# sensors.net
KiCad netlist of a schematic drawn in Altium Designer
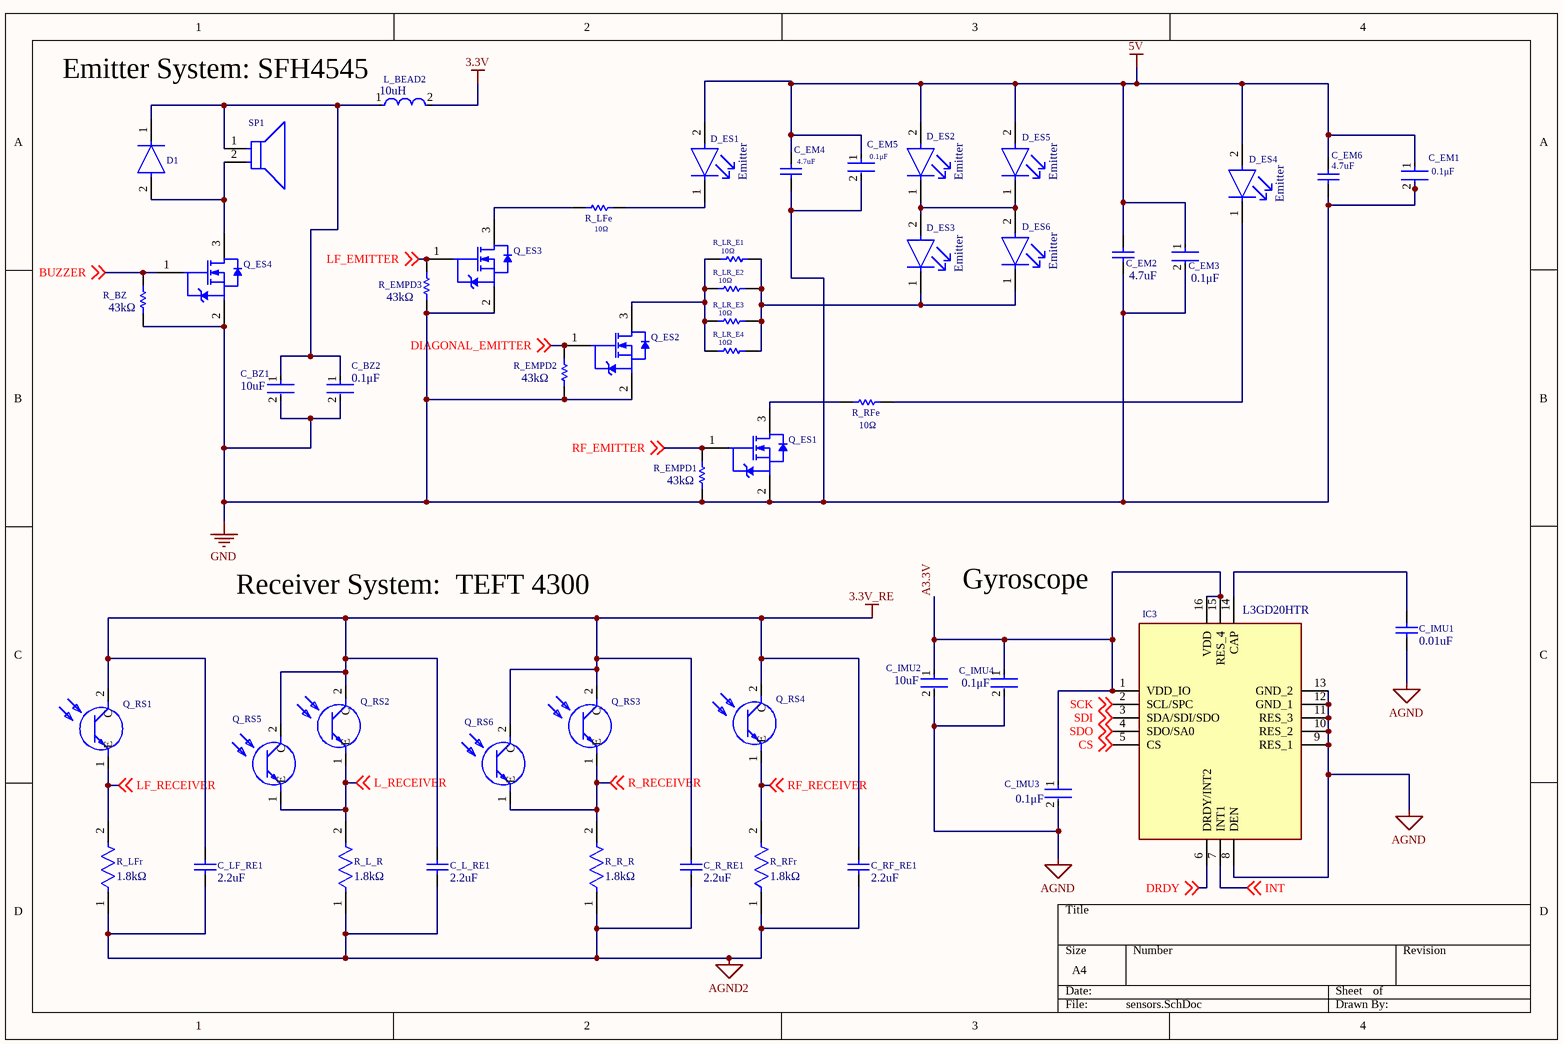
[diagram p0: sensors.SchDoc]

(export (version "E")
  (design (tool "Eeschema 10.0.6"))
  (components
    (comp (ref "C_BZ1")
      (value "10uF")
      (footprint "FP-C0805C-DG-MFG")
      (description "CAP CER 10UF 10V X5R 0805")
      (fields (field (name "TOLERANCE") "10%") (field (name "MANUFACTURER PART NUMBER") "C0805C106K8PACTU"))
      (libsource (lib "Altium Content Vault") (part "11868f565c42a9108669ba33697ecf6"))
    )
    (comp (ref "C_BZ2")
      (value "0.1μF")
      (footprint "FP-C0805C-DN-MFG")
      (description "CAP CER 0.1UF 10V 5% X7R 0805")
      (fields (field (name "MANUFACTURER") "KEMET") (field (name "TOLERANCE") "0.05"))
      (libsource (lib "Altium Content Vault") (part "b4654b650e69147ec39a6b967a45e02"))
    )
    (comp (ref "C_EM1")
      (value "0.1μF")
      (footprint "FP-C0805C-DN-MFG")
      (description "CAP CER 0.1UF 10V 5% X7R 0805")
      (fields (field (name "MANUFACTURER") "KEMET") (field (name "TOLERANCE") "0.05"))
      (libsource (lib "Altium Content Vault") (part "b4654b650e69147ec39a6b967a45e02"))
    )
    (comp (ref "C_EM2")
      (value "4.7uF")
      (footprint "CAPC2013X145X50NL20T25")
      (fields (field (name "PART NUMBER") "C0805C475M3PACTU") (field (name "MANUFACTURER") "Kemet"))
      (libsource (lib "Altium Content Vault") (part "CAP"))
    )
    (comp (ref "C_EM3")
      (value "0.1μF")
      (footprint "FP-C0805C-DN-MFG")
      (description "CAP CER 0.1UF 10V 5% X7R 0805")
      (fields (field (name "MANUFACTURER") "KEMET") (field (name "TOLERANCE") "0.05"))
      (libsource (lib "Altium Content Vault") (part "b4654b650e69147ec39a6b967a45e02"))
    )
    (comp (ref "C_EM4")
      (value "4.7uF")
      (footprint "CAPC2013X145X50NL20T25")
      (fields (field (name "PART NUMBER") "C0805C475M3PACTU") (field (name "MANUFACTURER") "Kemet"))
      (libsource (lib "Altium Content Vault") (part "CAP"))
    )
    (comp (ref "C_EM5")
      (value "0.1μF")
      (footprint "FP-C0805C-DN-MFG")
      (description "CAP CER 0.1UF 10V 5% X7R 0805")
      (fields (field (name "MANUFACTURER") "KEMET") (field (name "TOLERANCE") "0.05"))
      (libsource (lib "Altium Content Vault") (part "b4654b650e69147ec39a6b967a45e02"))
    )
    (comp (ref "C_EM6")
      (value "4.7uF")
      (footprint "CAPC2013X145X50NL20T25")
      (fields (field (name "PART NUMBER") "C0805C475M3PACTU") (field (name "MANUFACTURER") "Kemet"))
      (libsource (lib "Altium Content Vault") (part "CAP"))
    )
    (comp (ref "C_IMU1")
      (value "0.01uF")
      (footprint "CAPC2013X88X50LL20T25")
      (fields (field (name "MANUFACTURER") "Kemet") (field (name "PART NUMBER") "C0805C103K5RACTU"))
      (libsource (lib "Altium Content Vault") (part "CAP"))
    )
    (comp (ref "C_IMU2")
      (value "10uF")
      (footprint "FP-C0805C-DG-MFG")
      (description "CAP CER 10UF 10V X5R 0805")
      (fields (field (name "TOLERANCE") "10%") (field (name "MANUFACTURER PART NUMBER") "C0805C106K8PACTU"))
      (libsource (lib "Altium Content Vault") (part "11868f565c42a9108669ba33697ecf6"))
    )
    (comp (ref "C_IMU3")
      (value "0.1μF")
      (footprint "FP-C0805C-DN-MFG")
      (description "CAP CER 0.1UF 10V 5% X7R 0805")
      (fields (field (name "MANUFACTURER") "KEMET") (field (name "TOLERANCE") "0.05"))
      (libsource (lib "Altium Content Vault") (part "b4654b650e69147ec39a6b967a45e02"))
    )
    (comp (ref "C_IMU4")
      (value "0.1μF")
      (footprint "FP-C0805C-DN-MFG")
      (description "CAP CER 0.1UF 10V 5% X7R 0805")
      (fields (field (name "MANUFACTURER") "KEMET") (field (name "TOLERANCE") "0.05"))
      (libsource (lib "Altium Content Vault") (part "b4654b650e69147ec39a6b967a45e02"))
    )
    (comp (ref "C_LF_RE1")
      (value "2.2uF")
      (footprint "CAPC2013X145X50ML20T25")
      (fields (field (name "PART NUMBER") "C0805C225K9PACTU") (field (name "MANUFACTURER") "Kemet"))
      (libsource (lib "Altium Content Vault") (part "CAP"))
    )
    (comp (ref "C_L_RE1")
      (value "2.2uF")
      (footprint "CAPC2013X145X50ML20T25")
      (fields (field (name "PART NUMBER") "C0805C225K9PACTU") (field (name "MANUFACTURER") "Kemet"))
      (libsource (lib "Altium Content Vault") (part "CAP"))
    )
    (comp (ref "C_RF_RE1")
      (value "2.2uF")
      (footprint "CAPC2013X145X50ML20T25")
      (fields (field (name "PART NUMBER") "C0805C225K9PACTU") (field (name "MANUFACTURER") "Kemet"))
      (libsource (lib "Altium Content Vault") (part "CAP"))
    )
    (comp (ref "C_R_RE1")
      (value "2.2uF")
      (footprint "CAPC2013X145X50ML20T25")
      (fields (field (name "PART NUMBER") "C0805C225K9PACTU") (field (name "MANUFACTURER") "Kemet"))
      (libsource (lib "Altium Content Vault") (part "CAP"))
    )
    (comp (ref "D1")
      (value "1N4148W-TP")
      (footprint "FP-SOD-123-IPC_A")
      (description "DIODE GEN PURP 100V 150MA SOD123")
      (libsource (lib "Altium Content Vault") (part "d7152d700b627762746794eb795d46e"))
    )
    (comp (ref "D_ES1")
      (value "Emitter")
      (footprint "FP-SFH_4556-MFG")
      (description "EMITTER IR 950NM 100MA RADIAL")
      (fields (field (name "MANUFACTURER PART NUMBER") "SFH 4545") (field (name "MANUFACTURER") "Osram Opto"))
      (libsource (lib "Altium Content Vault") (part "8706943c75ba83719d021d2fdc84c58"))
    )
    (comp (ref "D_ES2")
      (value "Emitter")
      (footprint "FP-SFH_4556-MFG")
      (description "EMITTER IR 950NM 100MA RADIAL")
      (fields (field (name "MANUFACTURER PART NUMBER") "SFH 4545") (field (name "MANUFACTURER") "Osram Opto"))
      (libsource (lib "Altium Content Vault") (part "8706943c75ba83719d021d2fdc84c58"))
    )
    (comp (ref "D_ES3")
      (value "Emitter")
      (footprint "FP-SFH_4556-MFG")
      (description "EMITTER IR 950NM 100MA RADIAL")
      (fields (field (name "MANUFACTURER PART NUMBER") "SFH 4545") (field (name "MANUFACTURER") "Osram Opto"))
      (libsource (lib "Altium Content Vault") (part "8706943c75ba83719d021d2fdc84c58"))
    )
    (comp (ref "D_ES4")
      (value "Emitter")
      (footprint "FP-SFH_4556-MFG")
      (description "EMITTER IR 950NM 100MA RADIAL")
      (fields (field (name "MANUFACTURER PART NUMBER") "SFH 4545") (field (name "MANUFACTURER") "Osram Opto"))
      (libsource (lib "Altium Content Vault") (part "8706943c75ba83719d021d2fdc84c58"))
    )
    (comp (ref "D_ES5")
      (value "Emitter")
      (footprint "FP-SFH_4556-MFG")
      (description "EMITTER IR 950NM 100MA RADIAL")
      (fields (field (name "MANUFACTURER PART NUMBER") "SFH 4545") (field (name "MANUFACTURER") "Osram Opto"))
      (libsource (lib "Altium Content Vault") (part "8706943c75ba83719d021d2fdc84c58"))
    )
    (comp (ref "D_ES6")
      (value "Emitter")
      (footprint "FP-SFH_4556-MFG")
      (description "EMITTER IR 950NM 100MA RADIAL")
      (fields (field (name "MANUFACTURER PART NUMBER") "SFH 4545") (field (name "MANUFACTURER") "Osram Opto"))
      (libsource (lib "Altium Content Vault") (part "8706943c75ba83719d021d2fdc84c58"))
    )
    (comp (ref "IC3")
      (value "L3GD20HTR")
      (footprint "SamacSys:H3LIS100DLTR")
      (description "Integrated Circuit")
      (fields (field (name "MOUSER PART NUMBER") "511-L3GD20HTR"))
      (libsource (lib "*") (part "L3GD20HTR"))
    )
    (comp (ref "L_BEAD2")
      (value "10uH")
      (footprint "FP-LB2012-1_25-0_2-MFG")
      (description "SMD Inductors 10uH ±10% 0.15A 0.468Ω 0805")
      (fields (field (name "TOLERANCE") "10%") (field (name "Comment") "LBR2012T100K"))
      (libsource (lib "Altium Content Vault") (part "725321dda6339637d4d059423bc1c3c"))
    )
    (comp (ref "Q_ES1")
      (value "FDV303N")
      (footprint "FAIR-FDV303N-3_V")
      (fields (field (name "MANUFACTURER") "Fairchild"))
      (libsource (lib "Altium Content Vault") (part "NEMOS-GSD-3_D"))
    )
    (comp (ref "Q_ES2")
      (value "FDV303N")
      (footprint "FAIR-FDV303N-3_V")
      (fields (field (name "MANUFACTURER") "Fairchild"))
      (libsource (lib "Altium Content Vault") (part "NEMOS-GSD-3_D"))
    )
    (comp (ref "Q_ES3")
      (value "FDV303N")
      (footprint "FAIR-FDV303N-3_V")
      (fields (field (name "MANUFACTURER") "Fairchild"))
      (libsource (lib "Altium Content Vault") (part "NEMOS-GSD-3_D"))
    )
    (comp (ref "Q_ES4")
      (value "FDV303N")
      (footprint "FAIR-FDV303N-3_V")
      (fields (field (name "MANUFACTURER") "Fairchild"))
      (libsource (lib "Altium Content Vault") (part "NEMOS-GSD-3_D"))
    )
    (comp (ref "Q_RS1")
      (value "TEFT4300")
      (footprint "SamacSys:TEFT4300")
      (description "Phototransistor")
      (fields (field (name "MOUSER PART NUMBER") "782-TEFT4300"))
      (libsource (lib "*") (part "TEFT4300"))
    )
    (comp (ref "Q_RS2")
      (value "TEFT4300")
      (footprint "SamacSys:TEFT4300")
      (description "Phototransistor")
      (fields (field (name "MOUSER PART NUMBER") "782-TEFT4300"))
      (libsource (lib "*") (part "TEFT4300"))
    )
    (comp (ref "Q_RS3")
      (value "TEFT4300")
      (footprint "SamacSys:TEFT4300")
      (description "Phototransistor")
      (fields (field (name "MOUSER PART NUMBER") "782-TEFT4300"))
      (libsource (lib "*") (part "TEFT4300"))
    )
    (comp (ref "Q_RS4")
      (value "TEFT4300")
      (footprint "SamacSys:TEFT4300")
      (description "Phototransistor")
      (fields (field (name "MOUSER PART NUMBER") "782-TEFT4300"))
      (libsource (lib "*") (part "TEFT4300"))
    )
    (comp (ref "Q_RS5")
      (value "TEFT4300")
      (footprint "SamacSys:TEFT4300")
      (description "Phototransistor")
      (fields (field (name "MOUSER PART NUMBER") "782-TEFT4300"))
      (libsource (lib "*") (part "TEFT4300"))
    )
    (comp (ref "Q_RS6")
      (value "TEFT4300")
      (footprint "SamacSys:TEFT4300")
      (description "Phototransistor")
      (fields (field (name "MOUSER PART NUMBER") "782-TEFT4300"))
      (libsource (lib "*") (part "TEFT4300"))
    )
    (comp (ref "R_BZ")
      (value "43kΩ")
      (footprint "RESC1608X55X30NL20T20")
      (fields (field (name "PART NUMBER") "ERA3AEB433V") (field (name "MANUFACTURER") "Panasonic"))
      (libsource (lib "Altium Content Vault") (part "RES"))
    )
    (comp (ref "R_EMPD1")
      (value "43kΩ")
      (footprint "RESC1608X55X30NL20T20")
      (fields (field (name "PART NUMBER") "ERA3AEB433V") (field (name "MANUFACTURER") "Panasonic"))
      (libsource (lib "Altium Content Vault") (part "RES"))
    )
    (comp (ref "R_EMPD2")
      (value "43kΩ")
      (footprint "RESC1608X55X30NL20T20")
      (fields (field (name "PART NUMBER") "ERA3AEB433V") (field (name "MANUFACTURER") "Panasonic"))
      (libsource (lib "Altium Content Vault") (part "RES"))
    )
    (comp (ref "R_EMPD3")
      (value "43kΩ")
      (footprint "RESC1608X55X30NL20T20")
      (fields (field (name "PART NUMBER") "ERA3AEB433V") (field (name "MANUFACTURER") "Panasonic"))
      (libsource (lib "Altium Content Vault") (part "RES"))
    )
    (comp (ref "R_LFe")
      (value "10Ω")
      (footprint "RESC2013X70X40NL20T20")
      (fields (field (name "MANUFACTURER") "Panasonic") (field (name "PART NUMBER") "ERJ-6ENF10R0V"))
      (libsource (lib "Altium Content Vault") (part "RES"))
    )
    (comp (ref "R_LFr")
      (value "1.8kΩ")
      (footprint "FP-RN732A-MFG")
      (description "SMD Chip Resistor, Thin Film, 1.8KΩ, 100 V, 0805 [2012 Metric], 100 mW, 0.1%, RN73 Series")
      (fields
        (field (name "MANUFACTURER PART NUMBER") "RN73C2A1K91BTDF")
        (field (name "OCTOPART") "https://octopart.com/rn73c2a1k91btdf-te+connectivity-42431691")
      )
      (libsource (lib "Altium Content Vault") (part "1029c3af85768c4190bb7ad29bc67b5"))
    )
    (comp (ref "R_LR_E1")
      (value "10Ω")
      (footprint "RESC2013X70X40NL20T20")
      (fields (field (name "MANUFACTURER") "Panasonic") (field (name "PART NUMBER") "ERJ-6ENF10R0V"))
      (libsource (lib "Altium Content Vault") (part "RES"))
    )
    (comp (ref "R_LR_E2")
      (value "10Ω")
      (footprint "RESC2013X70X40NL20T20")
      (fields (field (name "MANUFACTURER") "Panasonic") (field (name "PART NUMBER") "ERJ-6ENF10R0V"))
      (libsource (lib "Altium Content Vault") (part "RES"))
    )
    (comp (ref "R_LR_E3")
      (value "10Ω")
      (footprint "RESC2013X70X40NL20T20")
      (fields (field (name "MANUFACTURER") "Panasonic") (field (name "PART NUMBER") "ERJ-6ENF10R0V"))
      (libsource (lib "Altium Content Vault") (part "RES"))
    )
    (comp (ref "R_LR_E4")
      (value "10Ω")
      (footprint "RESC2013X70X40NL20T20")
      (fields (field (name "MANUFACTURER") "Panasonic") (field (name "PART NUMBER") "ERJ-6ENF10R0V"))
      (libsource (lib "Altium Content Vault") (part "RES"))
    )
    (comp (ref "R_L_R")
      (value "1.8kΩ")
      (footprint "FP-RN732A-MFG")
      (description "SMD Chip Resistor, Thin Film, 1.8KΩ, 100 V, 0805 [2012 Metric], 100 mW, 0.1%, RN73 Series")
      (fields
        (field (name "MANUFACTURER PART NUMBER") "RN73C2A1K91BTDF")
        (field (name "OCTOPART") "https://octopart.com/rn73c2a1k91btdf-te+connectivity-42431691")
      )
      (libsource (lib "Altium Content Vault") (part "1029c3af85768c4190bb7ad29bc67b5"))
    )
    (comp (ref "R_RFe")
      (value "10Ω")
      (footprint "RESC2013X70X40NL20T20")
      (fields (field (name "MANUFACTURER") "Panasonic") (field (name "PART NUMBER") "ERJ-6ENF10R0V"))
      (libsource (lib "Altium Content Vault") (part "RES"))
    )
    (comp (ref "R_RFr")
      (value "1.8kΩ")
      (footprint "FP-RN732A-MFG")
      (description "SMD Chip Resistor, Thin Film, 1.8KΩ, 100 V, 0805 [2012 Metric], 100 mW, 0.1%, RN73 Series")
      (fields
        (field (name "MANUFACTURER PART NUMBER") "RN73C2A1K91BTDF")
        (field (name "OCTOPART") "https://octopart.com/rn73c2a1k91btdf-te+connectivity-42431691")
      )
      (libsource (lib "Altium Content Vault") (part "1029c3af85768c4190bb7ad29bc67b5"))
    )
    (comp (ref "R_R_R")
      (value "1.8kΩ")
      (footprint "FP-RN732A-MFG")
      (description "SMD Chip Resistor, Thin Film, 1.8KΩ, 100 V, 0805 [2012 Metric], 100 mW, 0.1%, RN73 Series")
      (fields
        (field (name "MANUFACTURER PART NUMBER") "RN73C2A1K91BTDF")
        (field (name "OCTOPART") "https://octopart.com/rn73c2a1k91btdf-te+connectivity-42431691")
      )
      (libsource (lib "Altium Content Vault") (part "1029c3af85768c4190bb7ad29bc67b5"))
    )
    (comp (ref "SP1")
      (value "AI-1223-TWT-3V-2-R")
      (footprint "FP-AI-1223-TWT-3V-2-R-MFG")
      (description "BUZZER MAGNETIC 3V 12MM TH")
      (libsource (lib "Altium Content Vault") (part "1973c4b650225fd2ddacaff6b763965"))
    )
  )
  (nets
    (net (code "1") (name "/A3.3V") (class "Default")
      (node (ref "C_IMU2") (pin "1") (pinfunction "1_1") (pintype "passive"))
      (node (ref "C_IMU3") (pin "1") (pinfunction "1_1") (pintype "passive"))
      (node (ref "C_IMU4") (pin "1") (pinfunction "1_1") (pintype "passive"))
      (node (ref "IC3") (pin "1") (pinfunction "VDD_IO_1") (pintype "passive"))
      (node (ref "IC3") (pin "15") (pinfunction "RES_4_15") (pintype "passive"))
      (node (ref "IC3") (pin "16") (pinfunction "VDD_16") (pintype "passive"))
    )
    (net (code "2") (name "3.3V") (class "Default")
      (node (ref "L_BEAD2") (pin "2") (pinfunction "2_2") (pintype "passive"))
    )
    (net (code "3") (name "3.3V_RE") (class "Default")
      (node (ref "C_LF_RE1") (pin "2") (pinfunction "2_2") (pintype "passive"))
      (node (ref "C_L_RE1") (pin "2") (pinfunction "2_2") (pintype "passive"))
      (node (ref "C_RF_RE1") (pin "2") (pinfunction "2_2") (pintype "passive"))
      (node (ref "C_R_RE1") (pin "2") (pinfunction "2_2") (pintype "passive"))
      (node (ref "Q_RS1") (pin "2") (pinfunction "C_2") (pintype "passive"))
      (node (ref "Q_RS2") (pin "2") (pinfunction "C_2") (pintype "passive"))
      (node (ref "Q_RS3") (pin "2") (pinfunction "C_2") (pintype "passive"))
      (node (ref "Q_RS4") (pin "2") (pinfunction "C_2") (pintype "passive"))
      (node (ref "Q_RS5") (pin "2") (pinfunction "C_2") (pintype "passive"))
      (node (ref "Q_RS6") (pin "2") (pinfunction "C_2") (pintype "passive"))
    )
    (net (code "4") (name "5V") (class "Default")
      (node (ref "C_EM1") (pin "1") (pinfunction "1_1") (pintype "passive"))
      (node (ref "C_EM2") (pin "2") (pinfunction "2_2") (pintype "passive"))
      (node (ref "C_EM3") (pin "1") (pinfunction "1_1") (pintype "passive"))
      (node (ref "C_EM4") (pin "2") (pinfunction "2_2") (pintype "passive"))
      (node (ref "C_EM5") (pin "1") (pinfunction "1_1") (pintype "passive"))
      (node (ref "C_EM6") (pin "2") (pinfunction "2_2") (pintype "passive"))
      (node (ref "D_ES1") (pin "2") (pinfunction "A_2") (pintype "passive"))
      (node (ref "D_ES2") (pin "2") (pinfunction "A_2") (pintype "passive"))
      (node (ref "D_ES4") (pin "2") (pinfunction "A_2") (pintype "passive"))
      (node (ref "D_ES5") (pin "2") (pinfunction "A_2") (pintype "passive"))
    )
    (net (code "5") (name "AGND") (class "Default")
      (node (ref "C_IMU1") (pin "1") (pinfunction "1_1") (pintype "passive"))
      (node (ref "C_IMU2") (pin "2") (pinfunction "2_2") (pintype "passive"))
      (node (ref "C_IMU3") (pin "2") (pinfunction "2_2") (pintype "passive"))
      (node (ref "C_IMU4") (pin "2") (pinfunction "2_2") (pintype "passive"))
      (node (ref "IC3") (pin "10") (pinfunction "RES_2_10") (pintype "passive"))
      (node (ref "IC3") (pin "11") (pinfunction "RES_3_11") (pintype "passive"))
      (node (ref "IC3") (pin "12") (pinfunction "GND_1_12") (pintype "passive"))
      (node (ref "IC3") (pin "13") (pinfunction "GND_2_13") (pintype "passive"))
      (node (ref "IC3") (pin "8") (pinfunction "DEN_8") (pintype "passive"))
      (node (ref "IC3") (pin "9") (pinfunction "RES_1_9") (pintype "passive"))
    )
    (net (code "6") (name "AGND2") (class "Default")
      (node (ref "C_LF_RE1") (pin "1") (pinfunction "1_1") (pintype "passive"))
      (node (ref "C_L_RE1") (pin "1") (pinfunction "1_1") (pintype "passive"))
      (node (ref "C_R_RE1") (pin "1") (pinfunction "1_1") (pintype "passive"))
      (node (ref "R_LFr") (pin "1") (pinfunction "1_1") (pintype "passive"))
      (node (ref "R_L_R") (pin "1") (pinfunction "1_1") (pintype "passive"))
      (node (ref "R_RFr") (pin "1") (pinfunction "1_1") (pintype "passive"))
      (node (ref "R_R_R") (pin "1") (pinfunction "1_1") (pintype "passive"))
    )
    (net (code "7") (name "BUZZER") (class "Default")
      (node (ref "Q_ES4") (pin "1") (pinfunction "G_1") (pintype "passive"))
      (node (ref "R_BZ") (pin "2") (pinfunction "2_2") (pintype "passive"))
    )
    (net (code "8") (name "CS") (class "Default")
      (node (ref "IC3") (pin "5") (pinfunction "CS_5") (pintype "passive"))
    )
    (net (code "9") (name "DIAGONAL_EMITTER") (class "Default")
      (node (ref "Q_ES2") (pin "1") (pinfunction "G_1") (pintype "passive"))
      (node (ref "R_EMPD2") (pin "2") (pinfunction "2_2") (pintype "passive"))
    )
    (net (code "10") (name "DRDY") (class "Default")
      (node (ref "IC3") (pin "6") (pinfunction "DRDY/INT2_6") (pintype "passive"))
    )
    (net (code "11") (name "GND") (class "Default")
      (node (ref "C_BZ1") (pin "2") (pinfunction "2_2") (pintype "passive"))
      (node (ref "C_BZ2") (pin "2") (pinfunction "2_2") (pintype "passive"))
      (node (ref "C_EM1") (pin "2") (pinfunction "2_2") (pintype "passive"))
      (node (ref "C_EM2") (pin "1") (pinfunction "1_1") (pintype "passive"))
      (node (ref "C_EM3") (pin "2") (pinfunction "2_2") (pintype "passive"))
      (node (ref "C_EM4") (pin "1") (pinfunction "1_1") (pintype "passive"))
      (node (ref "C_EM5") (pin "2") (pinfunction "2_2") (pintype "passive"))
      (node (ref "C_EM6") (pin "1") (pinfunction "1_1") (pintype "passive"))
      (node (ref "Q_ES1") (pin "2") (pinfunction "S_2") (pintype "passive"))
      (node (ref "Q_ES2") (pin "2") (pinfunction "S_2") (pintype "passive"))
      (node (ref "Q_ES3") (pin "2") (pinfunction "S_2") (pintype "passive"))
      (node (ref "Q_ES4") (pin "2") (pinfunction "S_2") (pintype "passive"))
      (node (ref "R_BZ") (pin "1") (pinfunction "1_1") (pintype "passive"))
      (node (ref "R_EMPD1") (pin "1") (pinfunction "1_1") (pintype "passive"))
      (node (ref "R_EMPD2") (pin "1") (pinfunction "1_1") (pintype "passive"))
      (node (ref "R_EMPD3") (pin "1") (pinfunction "1_1") (pintype "passive"))
    )
    (net (code "12") (name "INT") (class "Default")
      (node (ref "IC3") (pin "7") (pinfunction "INT1_7") (pintype "passive"))
    )
    (net (code "13") (name "LF_EMITTER") (class "Default")
      (node (ref "Q_ES3") (pin "1") (pinfunction "G_1") (pintype "passive"))
      (node (ref "R_EMPD3") (pin "2") (pinfunction "2_2") (pintype "passive"))
    )
    (net (code "14") (name "LF_RECEIVER") (class "Default")
      (node (ref "Q_RS1") (pin "1") (pinfunction "E_1") (pintype "passive"))
      (node (ref "R_LFr") (pin "2") (pinfunction "2_2") (pintype "passive"))
    )
    (net (code "15") (name "L_RECEIVER") (class "Default")
      (node (ref "Q_RS2") (pin "1") (pinfunction "E_1") (pintype "passive"))
      (node (ref "Q_RS5") (pin "1") (pinfunction "E_1") (pintype "passive"))
      (node (ref "R_L_R") (pin "2") (pinfunction "2_2") (pintype "passive"))
    )
    (net (code "16") (name "Net-(D1-A)") (class "Default")
      (node (ref "D1") (pin "2") (pinfunction "A_2") (pintype "passive"))
      (node (ref "Q_ES4") (pin "3") (pinfunction "D_3") (pintype "passive"))
      (node (ref "SP1") (pin "2") (pinfunction "A_2") (pintype "passive"))
    )
    (net (code "17") (name "Net-(D1-C)") (class "Default")
      (node (ref "C_BZ1") (pin "1") (pinfunction "1_1") (pintype "passive"))
      (node (ref "C_BZ2") (pin "1") (pinfunction "1_1") (pintype "passive"))
      (node (ref "D1") (pin "1") (pinfunction "C_1") (pintype "passive"))
      (node (ref "L_BEAD2") (pin "1") (pinfunction "1_1") (pintype "passive"))
      (node (ref "SP1") (pin "1") (pinfunction "C_1") (pintype "passive"))
    )
    (net (code "18") (name "Net-(D_ES1-C)") (class "Default")
      (node (ref "D_ES1") (pin "1") (pinfunction "C_1") (pintype "passive"))
      (node (ref "R_LFe") (pin "2") (pinfunction "2_2") (pintype "passive"))
    )
    (net (code "19") (name "Net-(D_ES2-C)") (class "Default")
      (node (ref "D_ES2") (pin "1") (pinfunction "C_1") (pintype "passive"))
      (node (ref "D_ES3") (pin "2") (pinfunction "A_2") (pintype "passive"))
      (node (ref "D_ES5") (pin "1") (pinfunction "C_1") (pintype "passive"))
      (node (ref "D_ES6") (pin "2") (pinfunction "A_2") (pintype "passive"))
    )
    (net (code "20") (name "Net-(D_ES3-C)") (class "Default")
      (node (ref "D_ES3") (pin "1") (pinfunction "C_1") (pintype "passive"))
      (node (ref "D_ES6") (pin "1") (pinfunction "C_1") (pintype "passive"))
      (node (ref "R_LR_E1") (pin "2") (pinfunction "2_2") (pintype "passive"))
      (node (ref "R_LR_E2") (pin "2") (pinfunction "2_2") (pintype "passive"))
      (node (ref "R_LR_E3") (pin "2") (pinfunction "2_2") (pintype "passive"))
      (node (ref "R_LR_E4") (pin "2") (pinfunction "2_2") (pintype "passive"))
    )
    (net (code "21") (name "Net-(D_ES4-C)") (class "Default")
      (node (ref "D_ES4") (pin "1") (pinfunction "C_1") (pintype "passive"))
      (node (ref "R_RFe") (pin "2") (pinfunction "2_2") (pintype "passive"))
    )
    (net (code "22") (name "Net-(IC3-CAP)") (class "Default")
      (node (ref "C_IMU1") (pin "2") (pinfunction "2_2") (pintype "passive"))
      (node (ref "IC3") (pin "14") (pinfunction "CAP_14") (pintype "passive"))
    )
    (net (code "23") (name "Net-(Q_ES1-D)") (class "Default")
      (node (ref "Q_ES1") (pin "3") (pinfunction "D_3") (pintype "passive"))
      (node (ref "R_RFe") (pin "1") (pinfunction "1_1") (pintype "passive"))
    )
    (net (code "24") (name "Net-(Q_ES2-D)") (class "Default")
      (node (ref "Q_ES2") (pin "3") (pinfunction "D_3") (pintype "passive"))
      (node (ref "R_LR_E1") (pin "1") (pinfunction "1_1") (pintype "passive"))
      (node (ref "R_LR_E2") (pin "1") (pinfunction "1_1") (pintype "passive"))
      (node (ref "R_LR_E3") (pin "1") (pinfunction "1_1") (pintype "passive"))
      (node (ref "R_LR_E4") (pin "1") (pinfunction "1_1") (pintype "passive"))
    )
    (net (code "25") (name "Net-(Q_ES3-D)") (class "Default")
      (node (ref "Q_ES3") (pin "3") (pinfunction "D_3") (pintype "passive"))
      (node (ref "R_LFe") (pin "1") (pinfunction "1_1") (pintype "passive"))
    )
    (net (code "26") (name "RF_EMITTER") (class "Default")
      (node (ref "Q_ES1") (pin "1") (pinfunction "G_1") (pintype "passive"))
      (node (ref "R_EMPD1") (pin "2") (pinfunction "2_2") (pintype "passive"))
    )
    (net (code "27") (name "RF_RECEIVER") (class "Default")
      (node (ref "Q_RS4") (pin "1") (pinfunction "E_1") (pintype "passive"))
      (node (ref "R_RFr") (pin "2") (pinfunction "2_2") (pintype "passive"))
    )
    (net (code "28") (name "R_RECEIVER") (class "Default")
      (node (ref "Q_RS3") (pin "1") (pinfunction "E_1") (pintype "passive"))
      (node (ref "Q_RS6") (pin "1") (pinfunction "E_1") (pintype "passive"))
      (node (ref "R_R_R") (pin "2") (pinfunction "2_2") (pintype "passive"))
    )
    (net (code "29") (name "SCK") (class "Default")
      (node (ref "IC3") (pin "2") (pinfunction "SCL/SPC_2") (pintype "passive"))
    )
    (net (code "30") (name "SDI") (class "Default")
      (node (ref "IC3") (pin "3") (pinfunction "SDA/SDI/SDO_3") (pintype "passive"))
    )
    (net (code "31") (name "SDO") (class "Default")
      (node (ref "IC3") (pin "4") (pinfunction "SDO/SA0_4") (pintype "passive"))
    )
    (net (code "32") (name "unconnected-(C_RF_RE1-Pad1)") (class "Default")
      (node (ref "C_RF_RE1") (pin "1") (pinfunction "1_1") (pintype "passive"))
    )
  )
)
